# MCU.net
KiCad netlist of a schematic drawn in Altium Designer
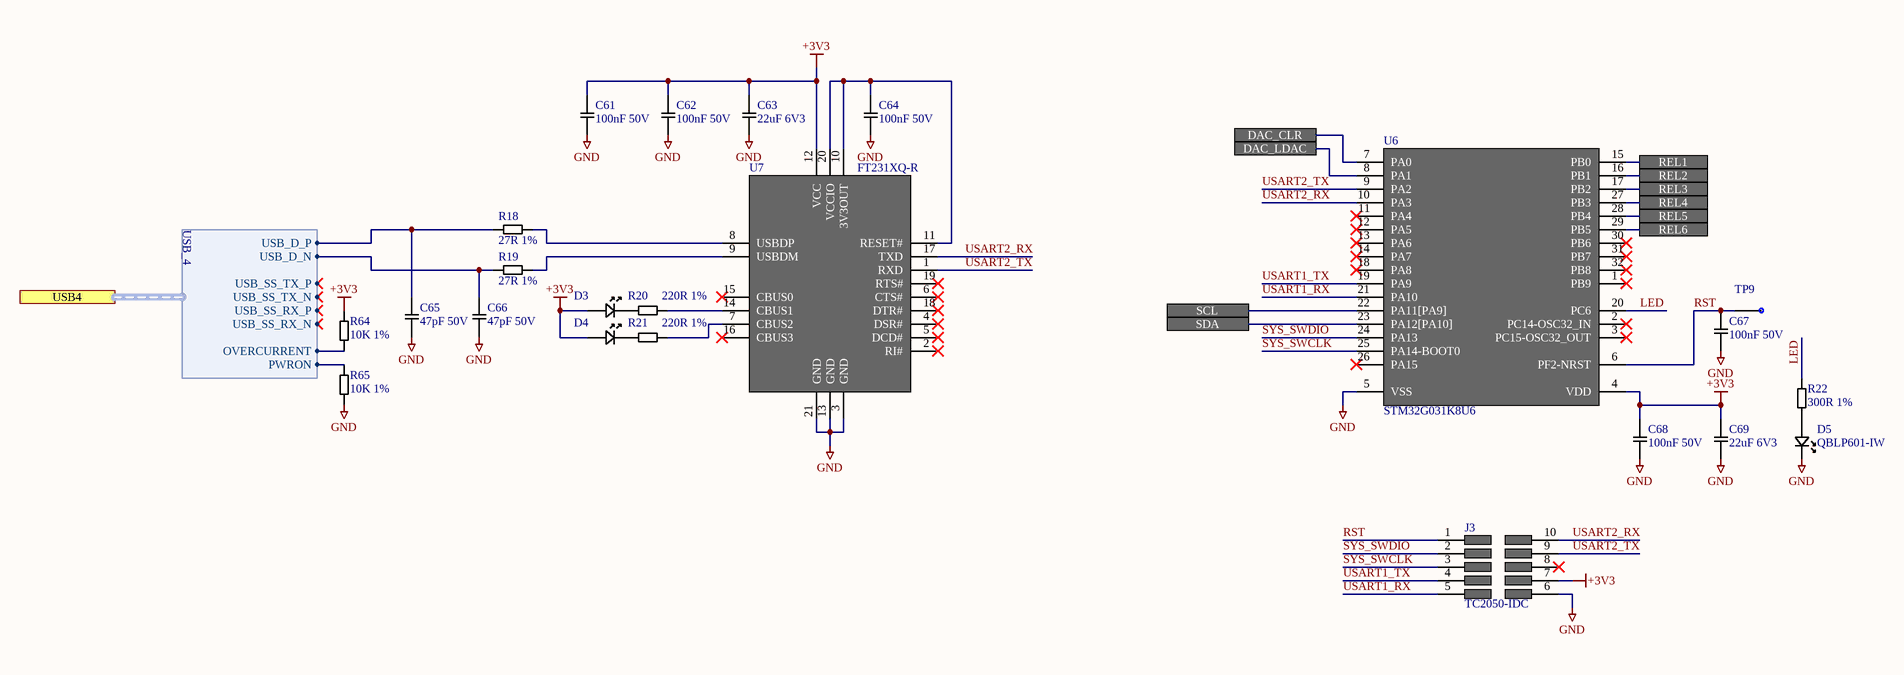
[diagram p0: MCU.SchDoc]

(export (version "E")
  (design (tool "Eeschema 10.0.6"))
  (components
    (comp (ref "C61")
      (value "100nF 50V")
      (footprint "CAPC1608X06N")
      (description "0.1 µF ±10% 50V Ceramic Capacitor X7R 0603 (1608 Metric)")
      (fields (field (name "MPN") "GCM188R71H104KA57D"))
      (libsource (lib "PCIe_Camera_Interface_Library") (part "100nF 50V"))
    )
    (comp (ref "C62")
      (value "100nF 50V")
      (footprint "CAPC1608X06N")
      (description "0.1 µF ±10% 50V Ceramic Capacitor X7R 0603 (1608 Metric)")
      (fields (field (name "MPN") "GCM188R71H104KA57D"))
      (libsource (lib "PCIe_Camera_Interface_Library") (part "100nF 50V"))
    )
    (comp (ref "C63")
      (value "22uF 6V3")
      (footprint "CAPC1608X06N")
      (description "22 µF ±20% 6.3V Ceramic Capacitor X5R 0603 (1608 Metric)")
      (fields (field (name "MPN") "GRM188R60J226MEA0D"))
      (libsource (lib "PCIe_Camera_Interface_Library") (part "22uF 6V3"))
    )
    (comp (ref "C64")
      (value "100nF 50V")
      (footprint "CAPC1608X06N")
      (description "0.1 µF ±10% 50V Ceramic Capacitor X7R 0603 (1608 Metric)")
      (fields (field (name "MPN") "GCM188R71H104KA57D"))
      (libsource (lib "PCIe_Camera_Interface_Library") (part "100nF 50V"))
    )
    (comp (ref "C65")
      (value "47pF 50V")
      (footprint "CAPC1608X06N")
      (description "47 pF ±5% 50V Ceramic Capacitor C0G, NP0 0603 (1608 Metric)")
      (fields (field (name "MPN") "CL10C470JB8NNNC"))
      (libsource (lib "PCIe_Camera_Interface_Library") (part "47pF 50V"))
    )
    (comp (ref "C66")
      (value "47pF 50V")
      (footprint "CAPC1608X06N")
      (description "47 pF ±5% 50V Ceramic Capacitor C0G, NP0 0603 (1608 Metric)")
      (fields (field (name "MPN") "CL10C470JB8NNNC"))
      (libsource (lib "PCIe_Camera_Interface_Library") (part "47pF 50V"))
    )
    (comp (ref "C67")
      (value "100nF 50V")
      (footprint "CAPC1608X06N")
      (description "0.1 µF ±10% 50V Ceramic Capacitor X7R 0603 (1608 Metric)")
      (fields (field (name "MPN") "GCM188R71H104KA57D"))
      (libsource (lib "PCIe_Camera_Interface_Library") (part "100nF 50V"))
    )
    (comp (ref "C68")
      (value "100nF 50V")
      (footprint "CAPC1608X06N")
      (description "0.1 µF ±10% 50V Ceramic Capacitor X7R 0603 (1608 Metric)")
      (fields (field (name "MPN") "GCM188R71H104KA57D"))
      (libsource (lib "PCIe_Camera_Interface_Library") (part "100nF 50V"))
    )
    (comp (ref "C69")
      (value "22uF 6V3")
      (footprint "CAPC1608X06N")
      (description "22 µF ±20% 6.3V Ceramic Capacitor X5R 0603 (1608 Metric)")
      (fields (field (name "MPN") "GRM188R60J226MEA0D"))
      (libsource (lib "PCIe_Camera_Interface_Library") (part "22uF 6V3"))
    )
    (comp (ref "D3")
      (value "QBLP601-IW")
      (footprint "LEDC1608X06N")
      (description "White LED Indication - Discrete 3.2V 0603 (1608 Metric)")
      (libsource (lib "PCIe_Camera_Interface_Library") (part "LED WHITE"))
    )
    (comp (ref "D4")
      (value "QBLP601-IW")
      (footprint "LEDC1608X06N")
      (description "White LED Indication - Discrete 3.2V 0603 (1608 Metric)")
      (libsource (lib "PCIe_Camera_Interface_Library") (part "LED WHITE"))
    )
    (comp (ref "D5")
      (value "QBLP601-IW")
      (footprint "LEDC1608X06N")
      (description "White LED Indication - Discrete 3.2V 0603 (1608 Metric)")
      (libsource (lib "PCIe_Camera_Interface_Library") (part "LED WHITE"))
    )
    (comp (ref "J3")
      (value "TC2050-IDC")
      (footprint "TAG_CONNECT")
      (libsource (lib "PCIe_Camera_Interface_Library") (part "TC2050-IDC"))
    )
    (comp (ref "R18")
      (value "27R 1%")
      (footprint "RESC1608X06N")
      (description "27 Ohms ±1% 0.1W, 1/10W Chip Resistor 0603 (1608 Metric) Moisture Resistant Thick Film")
      (fields (field (name "MPN") "RC0603FR-0727RL"))
      (libsource (lib "PCIe_Camera_Interface_Library") (part "27R 1%"))
    )
    (comp (ref "R19")
      (value "27R 1%")
      (footprint "RESC1608X06N")
      (description "27 Ohms ±1% 0.1W, 1/10W Chip Resistor 0603 (1608 Metric) Moisture Resistant Thick Film")
      (fields (field (name "MPN") "RC0603FR-0727RL"))
      (libsource (lib "PCIe_Camera_Interface_Library") (part "27R 1%"))
    )
    (comp (ref "R20")
      (value "220R 1%")
      (footprint "RESC1608X06N")
      (description "220 Ohms ±1% 0.1W, 1/10W Chip Resistor 0603 (1608 Metric) Automotive AEC-Q200 Thick Film")
      (fields (field (name "MPN") "ERJ-3EKF2200V"))
      (libsource (lib "PCIe_Camera_Interface_Library") (part "220R 1%"))
    )
    (comp (ref "R21")
      (value "220R 1%")
      (footprint "RESC1608X06N")
      (description "220 Ohms ±1% 0.1W, 1/10W Chip Resistor 0603 (1608 Metric) Automotive AEC-Q200 Thick Film")
      (fields (field (name "MPN") "ERJ-3EKF2200V"))
      (libsource (lib "PCIe_Camera_Interface_Library") (part "220R 1%"))
    )
    (comp (ref "R22")
      (value "300R 1%")
      (footprint "RESC1608X06N")
      (description "300 Ohms ±1% 0.1W, 1/10W Chip Resistor 0603 (1608 Metric) Automotive AEC-Q200 Thick Film")
      (fields (field (name "MPN") "ERJ-3EKF3000V"))
      (libsource (lib "PCIe_Camera_Interface_Library") (part "300R 1%"))
    )
    (comp (ref "R64")
      (value "10K 1%")
      (footprint "RESC1608X06N")
      (description "10 kOhms ±1% 0.1W, 1/10W Chip Resistor 0603 (1608 Metric) Automotive AEC-Q200 Thick Film")
      (fields (field (name "MPN") "ERJ-3EKF1002V"))
      (libsource (lib "PCIe_Camera_Interface_Library") (part "10K 1%"))
    )
    (comp (ref "R65")
      (value "10K 1%")
      (footprint "RESC1608X06N")
      (description "10 kOhms ±1% 0.1W, 1/10W Chip Resistor 0603 (1608 Metric) Automotive AEC-Q200 Thick Film")
      (fields (field (name "MPN") "ERJ-3EKF1002V"))
      (libsource (lib "PCIe_Camera_Interface_Library") (part "10K 1%"))
    )
    (comp (ref "TP9")
      (value "TP")
      (footprint "TP")
      (libsource (lib "PCIe_Camera_Interface_Library") (part "TP"))
    )
    (comp (ref "U6")
      (value "STM32G031K8U6")
      (footprint "UQFP32P50X50")
      (libsource (lib "PCIe_Camera_Interface_Library") (part "STM32G031K8U6"))
    )
    (comp (ref "U7")
      (value "FT231XQ-R")
      (footprint "QFN50P400X400X80-21N")
      (description "USB Bridge, USB to UART USB 2.0 UART Interface 20-QFN (4x4)")
      (libsource (lib "PCIe_Camera_Interface_Library") (part "FT231XQ-R"))
    )
  )
  (nets
    (net (code "2") (name "+3V3") (class "Default")
      (node (ref "C61") (pin "1") (pinfunction "1_1") (pintype "passive"))
      (node (ref "C62") (pin "1") (pinfunction "1_1") (pintype "passive"))
      (node (ref "C63") (pin "1") (pinfunction "1_1") (pintype "passive"))
      (node (ref "C68") (pin "1") (pinfunction "1_1") (pintype "passive"))
      (node (ref "C69") (pin "1") (pinfunction "1_1") (pintype "passive"))
      (node (ref "D3") (pin "1") (pinfunction "1_1") (pintype "passive"))
      (node (ref "D4") (pin "1") (pinfunction "1_1") (pintype "passive"))
      (node (ref "J3") (pin "7") (pinfunction "7_7") (pintype "passive"))
      (node (ref "R64") (pin "2") (pinfunction "2_2") (pintype "passive"))
      (node (ref "U6") (pin "4") (pinfunction "VDD_4") (pintype "passive"))
      (node (ref "U7") (pin "12") (pinfunction "VCC_12") (pintype "passive"))
    )
    (net (code "3") (name "/DAC_CLR") (class "Default")
      (node (ref "U6") (pin "7") (pinfunction "PA0_7") (pintype "passive"))
    )
    (net (code "4") (name "/DAC_LDAC") (class "Default")
      (node (ref "U6") (pin "8") (pinfunction "PA1_8") (pintype "passive"))
    )
    (net (code "5") (name "/LED") (class "Default")
      (node (ref "R22") (pin "2") (pinfunction "2_2") (pintype "passive"))
      (node (ref "U6") (pin "20") (pinfunction "PC6_20") (pintype "passive"))
    )
    (net (code "6") (name "/OVERCURRENT") (class "Default")
      (node (ref "R64") (pin "1") (pinfunction "1_1") (pintype "passive"))
    )
    (net (code "7") (name "/PWRON") (class "Default")
      (node (ref "R65") (pin "2") (pinfunction "2_2") (pintype "passive"))
    )
    (net (code "8") (name "/REL1") (class "Default")
      (node (ref "U6") (pin "15") (pinfunction "PB0_15") (pintype "passive"))
    )
    (net (code "9") (name "/REL2") (class "Default")
      (node (ref "U6") (pin "16") (pinfunction "PB1_16") (pintype "passive"))
    )
    (net (code "10") (name "/REL3") (class "Default")
      (node (ref "U6") (pin "17") (pinfunction "PB2_17") (pintype "passive"))
    )
    (net (code "11") (name "/REL4") (class "Default")
      (node (ref "U6") (pin "27") (pinfunction "PB3_27") (pintype "passive"))
    )
    (net (code "12") (name "/REL5") (class "Default")
      (node (ref "U6") (pin "28") (pinfunction "PB4_28") (pintype "passive"))
    )
    (net (code "13") (name "/REL6") (class "Default")
      (node (ref "U6") (pin "29") (pinfunction "PB5_29") (pintype "passive"))
    )
    (net (code "14") (name "/RST") (class "Default")
      (node (ref "C67") (pin "1") (pinfunction "1_1") (pintype "passive"))
      (node (ref "J3") (pin "1") (pinfunction "1_1") (pintype "passive"))
      (node (ref "TP9") (pin "1") (pinfunction "1_1") (pintype "passive"))
      (node (ref "U6") (pin "6") (pinfunction "PF2-NRST_6") (pintype "passive"))
    )
    (net (code "15") (name "/SCL") (class "Default")
      (node (ref "U6") (pin "22") (pinfunction "PA11[PA9]_22") (pintype "passive"))
    )
    (net (code "16") (name "/SDA") (class "Default")
      (node (ref "U6") (pin "23") (pinfunction "PA12[PA10]_23") (pintype "passive"))
    )
    (net (code "17") (name "/SYS_SWCLK") (class "Default")
      (node (ref "J3") (pin "3") (pinfunction "3_3") (pintype "passive"))
      (node (ref "U6") (pin "25") (pinfunction "PA14-BOOT0_25") (pintype "passive"))
    )
    (net (code "18") (name "/SYS_SWDIO") (class "Default")
      (node (ref "J3") (pin "2") (pinfunction "2_2") (pintype "passive"))
      (node (ref "U6") (pin "24") (pinfunction "PA13_24") (pintype "passive"))
    )
    (net (code "19") (name "/USART1_RX") (class "Default")
      (node (ref "J3") (pin "5") (pinfunction "5_5") (pintype "passive"))
      (node (ref "U6") (pin "21") (pinfunction "PA10_21") (pintype "passive"))
    )
    (net (code "20") (name "/USART1_TX") (class "Default")
      (node (ref "J3") (pin "4") (pinfunction "4_4") (pintype "passive"))
      (node (ref "U6") (pin "19") (pinfunction "PA9_19") (pintype "passive"))
    )
    (net (code "21") (name "/USART2_RX") (class "Default")
      (node (ref "J3") (pin "10") (pinfunction "10_10") (pintype "passive"))
      (node (ref "U6") (pin "10") (pinfunction "PA3_10") (pintype "passive"))
      (node (ref "U7") (pin "17") (pinfunction "TXD_17") (pintype "passive"))
    )
    (net (code "22") (name "/USART2_TX") (class "Default")
      (node (ref "J3") (pin "9") (pinfunction "9_9") (pintype "passive"))
      (node (ref "U6") (pin "9") (pinfunction "PA2_9") (pintype "passive"))
      (node (ref "U7") (pin "1") (pinfunction "RXD_1") (pintype "passive"))
    )
    (net (code "23") (name "/USB_D_N") (class "Default")
      (node (ref "C66") (pin "2") (pinfunction "2_2") (pintype "passive"))
      (node (ref "R19") (pin "1") (pinfunction "1_1") (pintype "passive"))
    )
    (net (code "24") (name "/USB_D_P") (class "Default")
      (node (ref "C65") (pin "2") (pinfunction "2_2") (pintype "passive"))
      (node (ref "R18") (pin "1") (pinfunction "1_1") (pintype "passive"))
    )
    (net (code "26") (name "GND") (class "Default")
      (node (ref "C61") (pin "2") (pinfunction "2_2") (pintype "passive"))
      (node (ref "C62") (pin "2") (pinfunction "2_2") (pintype "passive"))
      (node (ref "C63") (pin "2") (pinfunction "2_2") (pintype "passive"))
      (node (ref "C64") (pin "2") (pinfunction "2_2") (pintype "passive"))
      (node (ref "C65") (pin "1") (pinfunction "1_1") (pintype "passive"))
      (node (ref "C66") (pin "1") (pinfunction "1_1") (pintype "passive"))
      (node (ref "C67") (pin "2") (pinfunction "2_2") (pintype "passive"))
      (node (ref "C68") (pin "2") (pinfunction "2_2") (pintype "passive"))
      (node (ref "C69") (pin "2") (pinfunction "2_2") (pintype "passive"))
      (node (ref "D5") (pin "2") (pinfunction "2_2") (pintype "passive"))
      (node (ref "J3") (pin "6") (pinfunction "6_6") (pintype "passive"))
      (node (ref "R65") (pin "1") (pinfunction "1_1") (pintype "passive"))
      (node (ref "U6") (pin "5") (pinfunction "VSS_5") (pintype "passive"))
      (node (ref "U7") (pin "13") (pinfunction "GND_13") (pintype "passive"))
      (node (ref "U7") (pin "21") (pinfunction "GND_21") (pintype "passive"))
      (node (ref "U7") (pin "3") (pinfunction "GND_3") (pintype "passive"))
    )
    (net (code "27") (name "Net-(D3-Pad2)") (class "Default")
      (node (ref "D3") (pin "2") (pinfunction "2_2") (pintype "passive"))
      (node (ref "R20") (pin "1") (pinfunction "1_1") (pintype "passive"))
    )
    (net (code "28") (name "Net-(D4-Pad2)") (class "Default")
      (node (ref "D4") (pin "2") (pinfunction "2_2") (pintype "passive"))
      (node (ref "R21") (pin "1") (pinfunction "1_1") (pintype "passive"))
    )
    (net (code "29") (name "Net-(D5-Pad1)") (class "Default")
      (node (ref "D5") (pin "1") (pinfunction "1_1") (pintype "passive"))
      (node (ref "R22") (pin "1") (pinfunction "1_1") (pintype "passive"))
    )
    (net (code "30") (name "Net-(U7-3V3OUT)") (class "Default")
      (node (ref "C64") (pin "1") (pinfunction "1_1") (pintype "passive"))
      (node (ref "U7") (pin "10") (pinfunction "3V3OUT_10") (pintype "passive"))
      (node (ref "U7") (pin "11") (pinfunction "RESET#_11") (pintype "passive"))
      (node (ref "U7") (pin "20") (pinfunction "VCCIO_20") (pintype "passive"))
    )
    (net (code "31") (name "Net-(U7-CBUS1)") (class "Default")
      (node (ref "R20") (pin "2") (pinfunction "2_2") (pintype "passive"))
      (node (ref "U7") (pin "14") (pinfunction "CBUS1_14") (pintype "passive"))
    )
    (net (code "32") (name "Net-(U7-CBUS2)") (class "Default")
      (node (ref "R21") (pin "2") (pinfunction "2_2") (pintype "passive"))
      (node (ref "U7") (pin "7") (pinfunction "CBUS2_7") (pintype "passive"))
    )
    (net (code "33") (name "Net-(U7-USBDM)") (class "Default")
      (node (ref "R19") (pin "2") (pinfunction "2_2") (pintype "passive"))
      (node (ref "U7") (pin "9") (pinfunction "USBDM_9") (pintype "passive"))
    )
    (net (code "34") (name "Net-(U7-USBDP)") (class "Default")
      (node (ref "R18") (pin "2") (pinfunction "2_2") (pintype "passive"))
      (node (ref "U7") (pin "8") (pinfunction "USBDP_8") (pintype "passive"))
    )
    (net (code "35") (name "unconnected-(J3-Pad8)") (class "Default")
      (node (ref "J3") (pin "8") (pinfunction "8_8") (pintype "passive+no_connect"))
    )
    (net (code "36") (name "unconnected-(U6-PA4-Pad11)") (class "Default")
      (node (ref "U6") (pin "11") (pinfunction "PA4_11") (pintype "passive+no_connect"))
    )
    (net (code "37") (name "unconnected-(U6-PA5-Pad12)") (class "Default")
      (node (ref "U6") (pin "12") (pinfunction "PA5_12") (pintype "passive+no_connect"))
    )
    (net (code "38") (name "unconnected-(U6-PA6-Pad13)") (class "Default")
      (node (ref "U6") (pin "13") (pinfunction "PA6_13") (pintype "passive+no_connect"))
    )
    (net (code "39") (name "unconnected-(U6-PA7-Pad14)") (class "Default")
      (node (ref "U6") (pin "14") (pinfunction "PA7_14") (pintype "passive+no_connect"))
    )
    (net (code "40") (name "unconnected-(U6-PA8-Pad18)") (class "Default")
      (node (ref "U6") (pin "18") (pinfunction "PA8_18") (pintype "passive+no_connect"))
    )
    (net (code "41") (name "unconnected-(U6-PA15-Pad26)") (class "Default")
      (node (ref "U6") (pin "26") (pinfunction "PA15_26") (pintype "passive+no_connect"))
    )
    (net (code "42") (name "unconnected-(U6-PB6-Pad30)") (class "Default")
      (node (ref "U6") (pin "30") (pinfunction "PB6_30") (pintype "passive+no_connect"))
    )
    (net (code "43") (name "unconnected-(U6-PB7-Pad31)") (class "Default")
      (node (ref "U6") (pin "31") (pinfunction "PB7_31") (pintype "passive+no_connect"))
    )
    (net (code "44") (name "unconnected-(U6-PB8-Pad32)") (class "Default")
      (node (ref "U6") (pin "32") (pinfunction "PB8_32") (pintype "passive+no_connect"))
    )
    (net (code "45") (name "unconnected-(U6-PB9-Pad1)") (class "Default")
      (node (ref "U6") (pin "1") (pinfunction "PB9_1") (pintype "passive+no_connect"))
    )
    (net (code "46") (name "unconnected-(U6-PC14-OSC32_IN-Pad2)") (class "Default")
      (node (ref "U6") (pin "2") (pinfunction "PC14-OSC32_IN_2") (pintype "passive+no_connect"))
    )
    (net (code "47") (name "unconnected-(U6-PC15-OSC32_OUT-Pad3)") (class "Default")
      (node (ref "U6") (pin "3") (pinfunction "PC15-OSC32_OUT_3") (pintype "passive+no_connect"))
    )
    (net (code "48") (name "unconnected-(U7-CBUS0-Pad15)") (class "Default")
      (node (ref "U7") (pin "15") (pinfunction "CBUS0_15") (pintype "passive+no_connect"))
    )
    (net (code "49") (name "unconnected-(U7-CBUS3-Pad16)") (class "Default")
      (node (ref "U7") (pin "16") (pinfunction "CBUS3_16") (pintype "passive+no_connect"))
    )
    (net (code "50") (name "unconnected-(U7-CTS#-Pad6)") (class "Default")
      (node (ref "U7") (pin "6") (pinfunction "CTS#_6") (pintype "passive+no_connect"))
    )
    (net (code "51") (name "unconnected-(U7-DCD#-Pad5)") (class "Default")
      (node (ref "U7") (pin "5") (pinfunction "DCD#_5") (pintype "passive+no_connect"))
    )
    (net (code "52") (name "unconnected-(U7-DSR#-Pad4)") (class "Default")
      (node (ref "U7") (pin "4") (pinfunction "DSR#_4") (pintype "passive+no_connect"))
    )
    (net (code "53") (name "unconnected-(U7-DTR#-Pad18)") (class "Default")
      (node (ref "U7") (pin "18") (pinfunction "DTR#_18") (pintype "passive+no_connect"))
    )
    (net (code "54") (name "unconnected-(U7-RI#-Pad2)") (class "Default")
      (node (ref "U7") (pin "2") (pinfunction "RI#_2") (pintype "passive+no_connect"))
    )
    (net (code "55") (name "unconnected-(U7-RTS#-Pad19)") (class "Default")
      (node (ref "U7") (pin "19") (pinfunction "RTS#_19") (pintype "passive+no_connect"))
    )
  )
)
